# LED_Inducator.net
KiCad netlist of a schematic drawn in Altium Designer
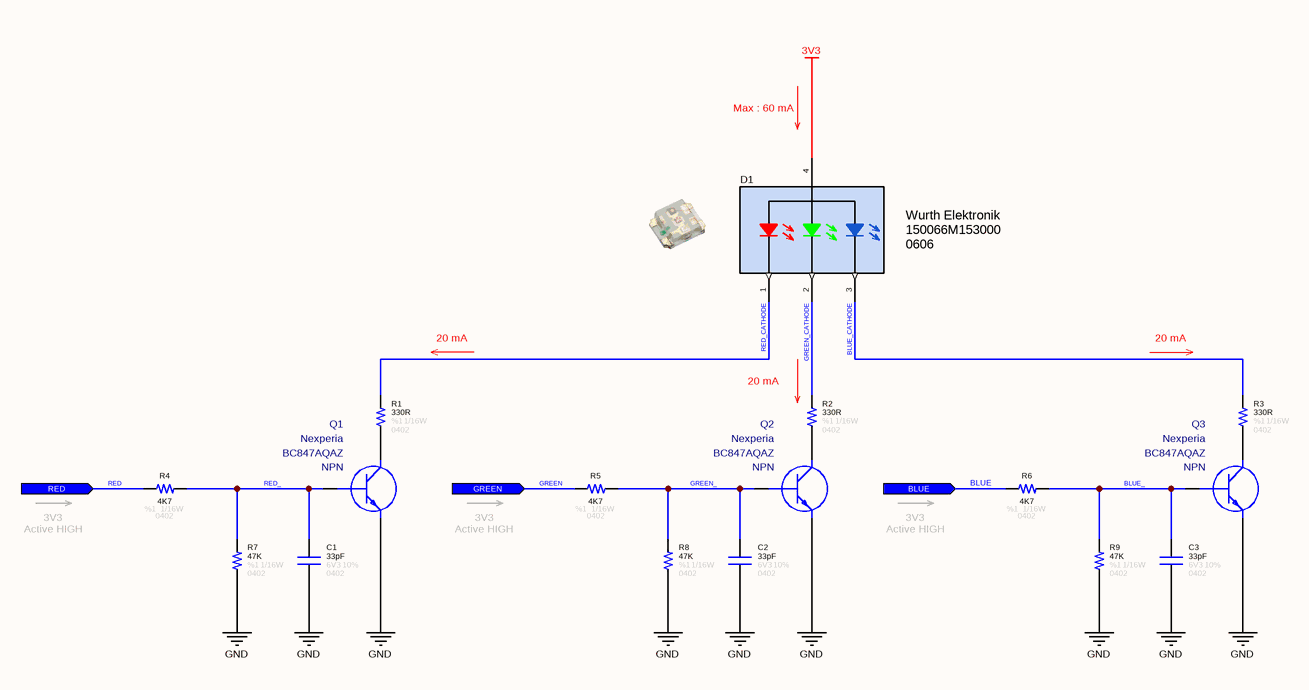
[diagram p0: LED Inducator.SchDoc]

(export (version "E")
  (design (tool "Eeschema 10.0.6"))
  (components
    (comp (ref "C1")
      (value "33pF")
      (footprint "CAPACITOR_0402")
      (description "Capacitor - 33pF [0402] (Ceramic)")
      (fields
        (field (name "MANUFACTURER PART NUMBER") "C0402C330J9RACAUTO")
        (field (name "TOLERANCE") "10%")
        (field (name "CASE") "0402")
        (field (name "VOLTAGE") "6V3")
      )
      (libsource (lib "P101DA_Library") (part "Capacitor - 33pF [0402-6V3]"))
    )
    (comp (ref "C2")
      (value "33pF")
      (footprint "CAPACITOR_0402")
      (description "Capacitor - 33pF [0402] (Ceramic)")
      (fields
        (field (name "MANUFACTURER PART NUMBER") "C0402C330J9RACAUTO")
        (field (name "TOLERANCE") "10%")
        (field (name "CASE") "0402")
        (field (name "VOLTAGE") "6V3")
      )
      (libsource (lib "P101DA_Library") (part "Capacitor - 33pF [0402-6V3]"))
    )
    (comp (ref "C3")
      (value "33pF")
      (footprint "CAPACITOR_0402")
      (description "Capacitor - 33pF [0402] (Ceramic)")
      (fields
        (field (name "MANUFACTURER PART NUMBER") "C0402C330J9RACAUTO")
        (field (name "TOLERANCE") "10%")
        (field (name "CASE") "0402")
        (field (name "VOLTAGE") "6V3")
      )
      (libsource (lib "P101DA_Library") (part "Capacitor - 33pF [0402-6V3]"))
    )
    (comp (ref "D1")
      (value "150066M153000")
      (footprint "Wurth_0606")
      (description "LED RGB DIFFUSED SMD")
      (fields
        (field (name "MANUFACTURER NAME") "Wurth Elektronik")
        (field (name "MANUFACTURER PART NUMBER") "150066M153000")
        (field (name "CASE") "0606")
      )
      (libsource (lib "P101DA_Library") (part "Diode - LED-RGB"))
    )
    (comp (ref "Q1")
      (value "BC847AQAZ")
      (footprint "SOT1215")
      (description "Bipolar NPN Transistors")
      (fields
        (field (name "MANUFACTURER NAME") "Nexperia")
        (field (name "MANUFACTURER PART NUMBER") "BC847AQAZ")
        (field (name "POLARITY") "NPN")
      )
      (libsource (lib "P101DA_Library") (part "Transistor - BC847"))
    )
    (comp (ref "Q2")
      (value "BC847AQAZ")
      (footprint "SOT1215")
      (description "Bipolar NPN Transistors")
      (fields
        (field (name "MANUFACTURER NAME") "Nexperia")
        (field (name "MANUFACTURER PART NUMBER") "BC847AQAZ")
        (field (name "POLARITY") "NPN")
      )
      (libsource (lib "P101DA_Library") (part "Transistor - BC847"))
    )
    (comp (ref "Q3")
      (value "BC847AQAZ")
      (footprint "SOT1215")
      (description "Bipolar NPN Transistors")
      (fields
        (field (name "MANUFACTURER NAME") "Nexperia")
        (field (name "MANUFACTURER PART NUMBER") "BC847AQAZ")
        (field (name "POLARITY") "NPN")
      )
      (libsource (lib "P101DA_Library") (part "Transistor - BC847"))
    )
    (comp (ref "R1")
      (value "330R")
      (footprint "RESISTOR_0402")
      (description "Thick Film Resistors - SMD 1/16 W 330 Ohm 1%")
      (fields
        (field (name "MANUFACTURER PART NUMBER") "CRCW0402330RFKED")
        (field (name "CASE") "0402")
        (field (name "TOLERANCE") "%1")
        (field (name "POWER") "1/16W")
        (field (name "Comment") "330R - 0402 - %1 - 1/16W")
      )
      (libsource (lib "P101DA_Library") (part "Resistor - 330R [0402]"))
    )
    (comp (ref "R2")
      (value "330R")
      (footprint "RESISTOR_0402")
      (description "Thick Film Resistors - SMD 1/16 W 330 Ohm 1%")
      (fields
        (field (name "MANUFACTURER PART NUMBER") "CRCW0402330RFKED")
        (field (name "CASE") "0402")
        (field (name "TOLERANCE") "%1")
        (field (name "POWER") "1/16W")
        (field (name "Comment") "330R - 0402 - %1 - 1/16W")
      )
      (libsource (lib "P101DA_Library") (part "Resistor - 330R [0402]"))
    )
    (comp (ref "R3")
      (value "330R")
      (footprint "RESISTOR_0402")
      (description "Thick Film Resistors - SMD 1/16 W 330 Ohm 1%")
      (fields
        (field (name "MANUFACTURER PART NUMBER") "CRCW0402330RFKED")
        (field (name "CASE") "0402")
        (field (name "TOLERANCE") "%1")
        (field (name "POWER") "1/16W")
        (field (name "Comment") "330R - 0402 - %1 - 1/16W")
      )
      (libsource (lib "P101DA_Library") (part "Resistor - 330R [0402]"))
    )
    (comp (ref "R4")
      (value "4K7")
      (footprint "RESISTOR_0402")
      (description "Thick Film Resistors - SMD 1/16 W 4.7 KOhm 1%")
      (fields
        (field (name "MANUFACTURER PART NUMBER") "CRCW04024K70FKED")
        (field (name "TOLERANCE") "%1")
        (field (name "CASE") "0402")
        (field (name "POWER") "1/16W")
        (field (name "Comment") "4K7 - 0402 - %1 - 1/16W")
      )
      (libsource (lib "P101DA_Library") (part "Resistor - 4K7 [0402]"))
    )
    (comp (ref "R5")
      (value "4K7")
      (footprint "RESISTOR_0402")
      (description "Thick Film Resistors - SMD 1/16 W 4.7 KOhm 1%")
      (fields
        (field (name "MANUFACTURER PART NUMBER") "CRCW04024K70FKED")
        (field (name "TOLERANCE") "%1")
        (field (name "CASE") "0402")
        (field (name "POWER") "1/16W")
        (field (name "Comment") "4K7 - 0402 - %1 - 1/16W")
      )
      (libsource (lib "P101DA_Library") (part "Resistor - 4K7 [0402]"))
    )
    (comp (ref "R6")
      (value "4K7")
      (footprint "RESISTOR_0402")
      (description "Thick Film Resistors - SMD 1/16 W 4.7 KOhm 1%")
      (fields
        (field (name "MANUFACTURER PART NUMBER") "CRCW04024K70FKED")
        (field (name "TOLERANCE") "%1")
        (field (name "CASE") "0402")
        (field (name "POWER") "1/16W")
        (field (name "Comment") "4K7 - 0402 - %1 - 1/16W")
      )
      (libsource (lib "P101DA_Library") (part "Resistor - 4K7 [0402]"))
    )
    (comp (ref "R7")
      (value "47K")
      (footprint "RESISTOR_0402")
      (description "Thick Film Resistors - SMD 1/16 W 47 KOhm 1%")
      (fields
        (field (name "MANUFACTURER PART NUMBER") "CRCW040247K0FKED")
        (field (name "TOLERANCE") "%1")
        (field (name "CASE") "0402")
        (field (name "POWER") "1/16W")
        (field (name "Comment") "47K - 0402 - %1 - 1/16W")
      )
      (libsource (lib "P101DA_Library") (part "Resistor - 47K [0402]"))
    )
    (comp (ref "R8")
      (value "47K")
      (footprint "RESISTOR_0402")
      (description "Thick Film Resistors - SMD 1/16 W 47 KOhm 1%")
      (fields
        (field (name "MANUFACTURER PART NUMBER") "CRCW040247K0FKED")
        (field (name "TOLERANCE") "%1")
        (field (name "CASE") "0402")
        (field (name "POWER") "1/16W")
        (field (name "Comment") "47K - 0402 - %1 - 1/16W")
      )
      (libsource (lib "P101DA_Library") (part "Resistor - 47K [0402]"))
    )
    (comp (ref "R9")
      (value "47K")
      (footprint "RESISTOR_0402")
      (description "Thick Film Resistors - SMD 1/16 W 47 KOhm 1%")
      (fields
        (field (name "MANUFACTURER PART NUMBER") "CRCW040247K0FKED")
        (field (name "TOLERANCE") "%1")
        (field (name "CASE") "0402")
        (field (name "POWER") "1/16W")
        (field (name "Comment") "47K - 0402 - %1 - 1/16W")
      )
      (libsource (lib "P101DA_Library") (part "Resistor - 47K [0402]"))
    )
  )
  (nets
    (net (code "1") (name "/BLUE") (class "Default")
      (node (ref "R6") (pin "2") (pinfunction "2_2") (pintype "passive"))
    )
    (net (code "2") (name "/BLUE_") (class "Default")
      (node (ref "C3") (pin "2") (pinfunction "2_2") (pintype "passive"))
      (node (ref "Q3") (pin "1") (pinfunction "B_1") (pintype "passive"))
      (node (ref "R6") (pin "1") (pinfunction "1_1") (pintype "passive"))
      (node (ref "R9") (pin "2") (pinfunction "2_2") (pintype "passive"))
    )
    (net (code "3") (name "/BLUE_CATHODE") (class "Default")
      (node (ref "D1") (pin "3") (pinfunction "3_3") (pintype "output"))
      (node (ref "R3") (pin "2") (pinfunction "2_2") (pintype "passive"))
    )
    (net (code "4") (name "/GREEN") (class "Default")
      (node (ref "R5") (pin "2") (pinfunction "2_2") (pintype "passive"))
    )
    (net (code "5") (name "/GREEN_") (class "Default")
      (node (ref "C2") (pin "2") (pinfunction "2_2") (pintype "passive"))
      (node (ref "Q2") (pin "1") (pinfunction "B_1") (pintype "passive"))
      (node (ref "R5") (pin "1") (pinfunction "1_1") (pintype "passive"))
      (node (ref "R8") (pin "2") (pinfunction "2_2") (pintype "passive"))
    )
    (net (code "6") (name "/GREEN_CATHODE") (class "Default")
      (node (ref "D1") (pin "2") (pinfunction "2_2") (pintype "output"))
      (node (ref "R2") (pin "2") (pinfunction "2_2") (pintype "passive"))
    )
    (net (code "7") (name "/RED") (class "Default")
      (node (ref "R4") (pin "2") (pinfunction "2_2") (pintype "passive"))
    )
    (net (code "8") (name "/RED_") (class "Default")
      (node (ref "C1") (pin "2") (pinfunction "2_2") (pintype "passive"))
      (node (ref "Q1") (pin "1") (pinfunction "B_1") (pintype "passive"))
      (node (ref "R4") (pin "1") (pinfunction "1_1") (pintype "passive"))
      (node (ref "R7") (pin "2") (pinfunction "2_2") (pintype "passive"))
    )
    (net (code "9") (name "/RED_CATHODE") (class "Default")
      (node (ref "D1") (pin "1") (pinfunction "1_1") (pintype "output"))
      (node (ref "R1") (pin "2") (pinfunction "2_2") (pintype "passive"))
    )
    (net (code "10") (name "3V3") (class "Default")
      (node (ref "D1") (pin "4") (pinfunction "4_4") (pintype "power_in"))
    )
    (net (code "11") (name "GND") (class "Default")
      (node (ref "C1") (pin "1") (pinfunction "1_1") (pintype "passive"))
      (node (ref "C2") (pin "1") (pinfunction "1_1") (pintype "passive"))
      (node (ref "C3") (pin "1") (pinfunction "1_1") (pintype "passive"))
      (node (ref "Q1") (pin "2") (pinfunction "E_2") (pintype "passive"))
      (node (ref "Q2") (pin "2") (pinfunction "E_2") (pintype "passive"))
      (node (ref "Q3") (pin "2") (pinfunction "E_2") (pintype "passive"))
      (node (ref "R7") (pin "1") (pinfunction "1_1") (pintype "passive"))
      (node (ref "R8") (pin "1") (pinfunction "1_1") (pintype "passive"))
      (node (ref "R9") (pin "1") (pinfunction "1_1") (pintype "passive"))
    )
    (net (code "12") (name "Net-(Q1-C)") (class "Default")
      (node (ref "Q1") (pin "3") (pinfunction "C_3") (pintype "passive"))
      (node (ref "R1") (pin "1") (pinfunction "1_1") (pintype "passive"))
    )
    (net (code "13") (name "Net-(Q2-C)") (class "Default")
      (node (ref "Q2") (pin "3") (pinfunction "C_3") (pintype "passive"))
      (node (ref "R2") (pin "1") (pinfunction "1_1") (pintype "passive"))
    )
    (net (code "14") (name "Net-(Q3-C)") (class "Default")
      (node (ref "Q3") (pin "3") (pinfunction "C_3") (pintype "passive"))
      (node (ref "R3") (pin "1") (pinfunction "1_1") (pintype "passive"))
    )
  )
)
